# SCH.net
KiCad netlist of a schematic drawn in Altium Designer
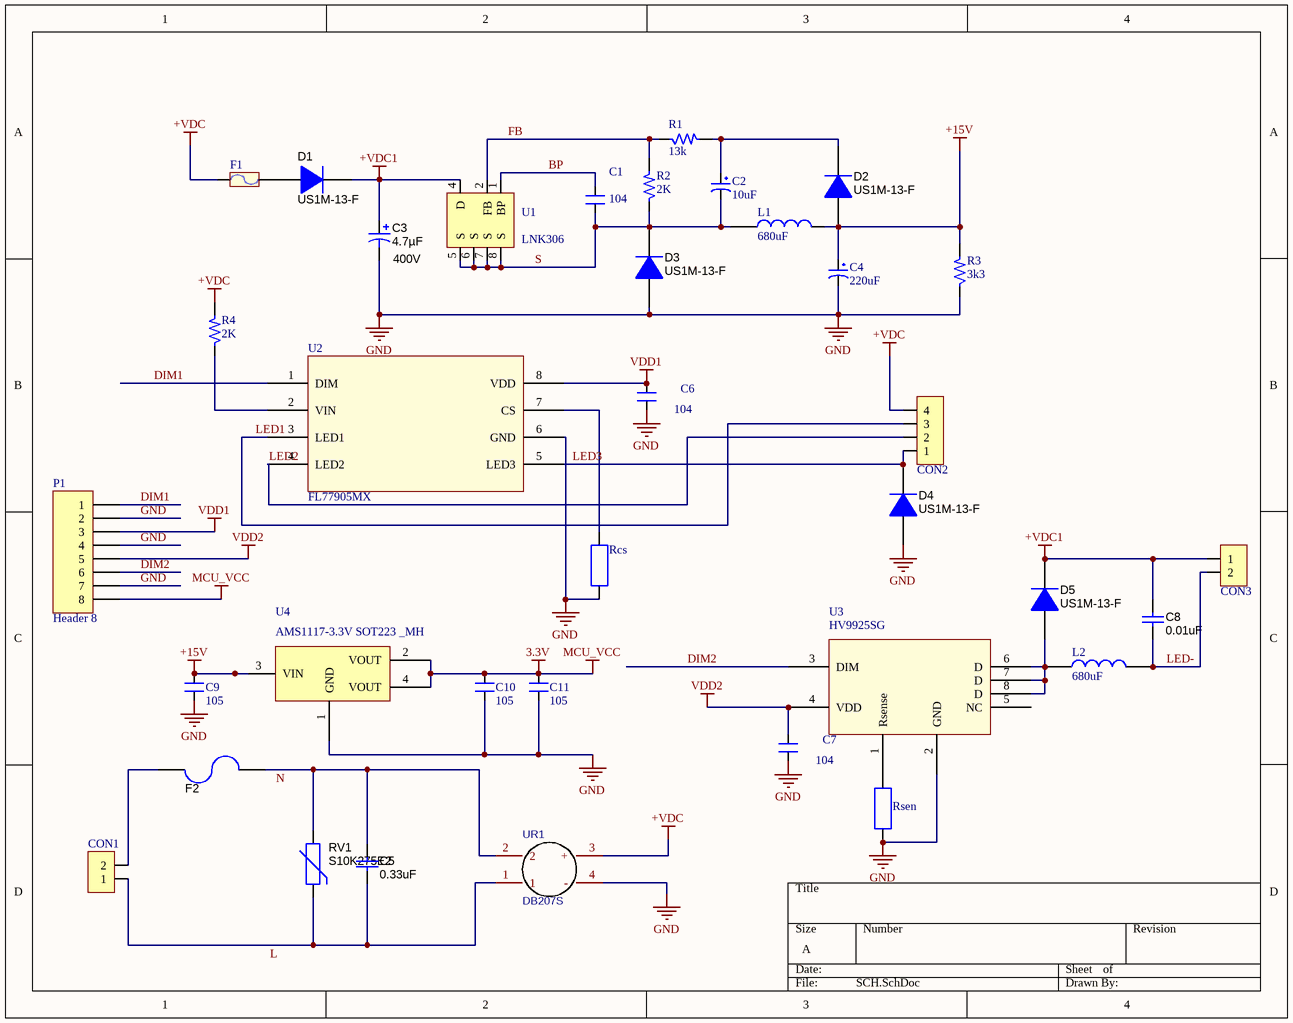
[diagram p0: SCH.SchDoc]

(export (version "E")
  (design (tool "Eeschema 10.0.6"))
  (components
    (comp (ref "C1")
      (value "104")
      (footprint "0805_Cap")
      (description "Cap SMD")
      (libsource (lib "hatcatbietbay") (part "CM"))
    )
    (comp (ref "C2")
      (value "10uF")
      (footprint "TU_NHOM_10uF_MH")
      (description "TU_NHOM_10uF_25V_MH")
      (libsource (lib "MH_DA_THU_VIEN_16122016") (part "TU_NHOM_10uF_25V_MH"))
    )
    (comp (ref "C3")
      (value "400AX6R8M8x11")
      (footprint "CAP-PANACAP-G-GENERIC")
      (description "CAP, AL, 6.8uF, 400V, +/-20%, TH")
      (fields
        (field (name "VALUEDISPLAYED") "4.7µF")
        (field (name "MANUFACTURER") "Rubycon")
        (field (name "VALUE2") "400V")
        (field (name "PUBLISHER") "Texas Instruments")
      )
      (libsource (lib "Capacitor_Aluminum") (part "400AX6R8M8x11"))
    )
    (comp (ref "C4")
      (value "220uF")
      (footprint "TU_NHOM_2.5_MH")
      (description "TU_NHOM_220uF_25V_MH")
      (libsource (lib "MH_DA_THU_VIEN_16122016") (part "TU_NHOM_220uF_25V_MH"))
    )
    (comp (ref "C5")
      (value "0.33uF")
      (footprint "B32922_12mm")
      (description "CAP FILM 0.33UF 630VDC RADIAL")
      (fields
        (field (name "PARTNUMBER") "B32922C3334M189")
        (field (name "MANUFACTURER") "EPCOS(TDK)")
        (field (name "SYMBOLCREATOR") "x0199378")
      )
      (libsource (lib "All-Final Symbols") (part "BFC233620154"))
    )
    (comp (ref "C6")
      (value "104")
      (footprint "0805_HV")
      (description "Cap SMD")
      (libsource (lib "hatcatbietbay") (part "CM"))
    )
    (comp (ref "C7")
      (value "104")
      (footprint "0805_HV")
      (description "Cap SMD")
      (libsource (lib "hatcatbietbay") (part "CM"))
    )
    (comp (ref "C8")
      (value "0.01uF")
      (footprint "B32922_12mm")
      (description "CAP FILM 0.33UF 630VDC RADIAL")
      (fields
        (field (name "PARTNUMBER") "B32922C3334M189")
        (field (name "MANUFACTURER") "EPCOS(TDK)")
        (field (name "SYMBOLCREATOR") "x0199378")
      )
      (libsource (lib "All-Final Symbols") (part "BFC233620154"))
    )
    (comp (ref "C9")
      (value "105")
      (footprint "0805_HV")
      (description "Cap SMD")
      (libsource (lib "hatcatbietbay") (part "CM"))
    )
    (comp (ref "C10")
      (value "105")
      (footprint "0805_HV")
      (description "Cap SMD")
      (libsource (lib "hatcatbietbay") (part "CM"))
    )
    (comp (ref "C11")
      (value "105")
      (footprint "0805_HV")
      (description "Cap SMD")
      (libsource (lib "hatcatbietbay") (part "CM"))
    )
    (comp (ref "CON1")
      (value "CON 2 EDG 5.08_MH")
      (footprint "CON 2 EDG 5.08")
      (description "CON 2 EDG 5.08 (xanh cong)")
      (libsource (lib "mySch") (part "CON 2 EDG 5.08_MH"))
    )
    (comp (ref "CON2")
      (value "CON 4 EDG 5.08_MH")
      (footprint "Con 4 EDG 5.08")
      (description "CON 4 EDG 5.08 (xanh cong)")
      (libsource (lib "MH_DA_THU_VIEN_16122016") (part "CON 4 EDG 5.08_MH"))
    )
    (comp (ref "CON3")
      (value "CON 2 EDG 5.08_MH")
      (footprint "CON 2 EDG 5.08")
      (description "CON 2 EDG 5.08 (xanh cong)")
      (libsource (lib "") (part "CON 2 EDG 5.08_MH_1"))
    )
    (comp (ref "D1")
      (value "US1M-13-F")
      (footprint "SMB")
      (description "Diode, Ultrafast, 600V, 1A, SMB")
      (fields
        (field (name "PARTNUMBER") "US1M-13-F")
        (field (name "MANUFACTURER") "Diodes Inc.")
        (field (name "PUBLISHER") "Texas Instruments")
      )
      (libsource (lib "Diode") (part "MURS160-13-F"))
    )
    (comp (ref "D2")
      (value "US1M-13-F")
      (footprint "SMB")
      (description "Diode, Ultrafast, 600V, 1A, SMB")
      (fields
        (field (name "PARTNUMBER") "US1M-13-F")
        (field (name "MANUFACTURER") "Diodes Inc.")
        (field (name "PUBLISHER") "Texas Instruments")
      )
      (libsource (lib "Diode") (part "MURS160-13-F"))
    )
    (comp (ref "D3")
      (value "US1M-13-F")
      (footprint "SMB")
      (description "Diode, Ultrafast, 600V, 1A, SMB")
      (fields
        (field (name "PARTNUMBER") "US1M-13-F")
        (field (name "MANUFACTURER") "Diodes Inc.")
        (field (name "PUBLISHER") "Texas Instruments")
      )
      (libsource (lib "Diode") (part "MURS160-13-F"))
    )
    (comp (ref "D4")
      (value "US1M-13-F")
      (footprint "SMB")
      (description "Diode, Ultrafast, 600V, 1A, SMB")
      (fields
        (field (name "PARTNUMBER") "US1M-13-F")
        (field (name "MANUFACTURER") "Diodes Inc.")
        (field (name "PUBLISHER") "Texas Instruments")
      )
      (libsource (lib "Diode") (part "MURS160-13-F"))
    )
    (comp (ref "D5")
      (value "US1M-13-F")
      (footprint "SMB")
      (description "Diode, Ultrafast, 600V, 1A, SMB")
      (fields
        (field (name "PARTNUMBER") "US1M-13-F")
        (field (name "MANUFACTURER") "Diodes Inc.")
        (field (name "PUBLISHER") "Texas Instruments")
      )
      (libsource (lib "Diode") (part "MURS160-13-F"))
    )
    (comp (ref "F1")
      (value "FUSE_AUTO_0.5A 8V 1206_MH")
      (footprint "FUSE 1206")
      (description "Fuse")
      (libsource (lib "MH_DA_THU_VIEN_16122016") (part "FUSE_AUTO_0.5A 8V 1206_MH"))
    )
    (comp (ref "F2")
      (value "37015000430")
      (footprint "Fuse 5x20")
      (description "FUSE BOARD MOUNT 5A 250VAC RAD")
      (fields (field (name "MANUFACTURER") "Littelfuse Inc") (field (name "PUBLISHER") "Texas Instruments"))
      (libsource (lib "Fuse") (part "0216008.MXESPP"))
    )
    (comp (ref "L1")
      (value "680uF")
      (footprint "Inductor 4.5x5")
      (libsource (lib "MH_DA_THU_VIEN_16122016") (part "Inductor 4.5x5_MH"))
    )
    (comp (ref "L2")
      (value "680uF")
      (footprint "Inductor 4.5x5")
      (libsource (lib "MH_DA_THU_VIEN_16122016") (part "Inductor 4.5x5_MH"))
    )
    (comp (ref "P1")
      (value "Header 8")
      (footprint "HDR1X8")
      (description "Header, 8-Pin")
      (fields (field (name "PUBLISHER") "Altium Limited"))
      (libsource (lib "Miscellaneous Connectors") (part "Header 8"))
    )
    (comp (ref "R1")
      (value "13k")
      (footprint "0805_R")
      (description "Resistor 1/4W")
      (libsource (lib "hatcatbietbay") (part "R"))
    )
    (comp (ref "R2")
      (value "2K")
      (footprint "0805_R")
      (description "Resistor 1/4W")
      (libsource (lib "hatcatbietbay") (part "R"))
    )
    (comp (ref "R3")
      (value "3k3")
      (footprint "0805_R")
      (description "Resistor 1/4W")
      (libsource (lib "hatcatbietbay") (part "R"))
    )
    (comp (ref "R4")
      (value "2K")
      (footprint "1206")
      (description "Resistor 1/4W")
      (libsource (lib "hatcatbietbay") (part "R"))
    )
    (comp (ref "Rcs")
      (value "TRO_CS_2W_MH")
      (footprint "TRO_VACH_2W")
      (libsource (lib "MH_DA_THU_VIEN_16122016") (part "TRO_CS_2W_MH"))
    )
    (comp (ref "Rsen")
      (value "TRO_CS_2W_MH")
      (footprint "TRO_VACH_2W")
      (libsource (lib "MH_DA_THU_VIEN_16122016") (part "TRO_CS_2W_MH"))
    )
    (comp (ref "RV1")
      (value "S10K275E2")
      (footprint "VAR_S10K275E2")
      (description "Varistor 275V RMS 10MM Radial, TH")
      (fields
        (field (name "MANUFACTURER") "EPCOS Inc")
        (field (name "SYMBOLCREATOR") "a0412235")
        (field (name "PUBLISHER") "Texas Instruments")
      )
      (libsource (lib "Other_Passive") (part "S10K275E2"))
    )
    (comp (ref "U1") (value "LNK306") (footprint "SOP 7") (libsource (lib "LNK304") (part "Component_1")))
    (comp (ref "U2") (value "FL77905MX") (footprint "SOP 8") (libsource (lib "Schlib1") (part "FL77905")))
    (comp (ref "U3") (value "HV9925SG") (footprint "SOP 8") (libsource (lib "Schlib1") (part "HV9925")))
    (comp (ref "U4")
      (value "AMS1117-3.3V SOT223 _MH")
      (footprint "SOT223")
      (libsource (lib "MH_DA_THU_VIEN_16122016") (part "AMS1117-3.3V SOT223 _MH"))
    )
    (comp (ref "UR1")
      (value "DB207S")
      (footprint "DB207S")
      (fields (field (name "BOM_SUPPLIER PART") "C84160"))
      (libsource (lib "mySch") (part "DB207S"))
    )
  )
  (nets
    (net (code "1") (name "+15V") (class "Default")
      (node (ref "C4") (pin "1") (pinfunction "1_1") (pintype "passive"))
      (node (ref "C9") (pin "2") (pinfunction "2_2") (pintype "passive"))
      (node (ref "D2") (pin "2") (pinfunction "A_2") (pintype "passive"))
      (node (ref "L1") (pin "2") (pinfunction "2_2") (pintype "passive"))
      (node (ref "R3") (pin "2") (pinfunction "2_2") (pintype "passive"))
      (node (ref "U4") (pin "3") (pinfunction "VIN_3") (pintype "passive"))
    )
    (net (code "2") (name "+VDC") (class "Default")
      (node (ref "CON2") (pin "4") (pinfunction "4_4") (pintype "passive"))
      (node (ref "F1") (pin "1") (pinfunction "1_1") (pintype "passive"))
      (node (ref "R4") (pin "2") (pinfunction "2_2") (pintype "passive"))
      (node (ref "UR1") (pin "3") (pinfunction "+_3") (pintype "passive"))
    )
    (net (code "3") (name "+VDC1") (class "Default")
      (node (ref "C3") (pin "1") (pinfunction "+_1") (pintype "passive"))
      (node (ref "C8") (pin "2") (pinfunction "2_2") (pintype "passive"))
      (node (ref "CON3") (pin "1") (pinfunction "1_1") (pintype "passive"))
      (node (ref "D1") (pin "1") (pinfunction "K_1") (pintype "passive"))
      (node (ref "D5") (pin "1") (pinfunction "K_1") (pintype "passive"))
      (node (ref "U1") (pin "4") (pinfunction "D_4") (pintype "passive"))
    )
    (net (code "4") (name "/BP") (class "Default")
      (node (ref "C1") (pin "2") (pinfunction "2_2") (pintype "passive"))
      (node (ref "U1") (pin "1") (pinfunction "BP_1") (pintype "passive"))
    )
    (net (code "5") (name "/DIM1") (class "Default")
      (node (ref "P1") (pin "1") (pinfunction "1_1") (pintype "passive"))
      (node (ref "U2") (pin "1") (pinfunction "DIM_1") (pintype "passive"))
    )
    (net (code "6") (name "/DIM2") (class "Default")
      (node (ref "P1") (pin "6") (pinfunction "6_6") (pintype "passive"))
      (node (ref "U3") (pin "3") (pinfunction "DIM_3") (pintype "passive"))
    )
    (net (code "7") (name "/FB") (class "Default")
      (node (ref "R1") (pin "1") (pinfunction "1_1") (pintype "passive"))
      (node (ref "R2") (pin "2") (pinfunction "2_2") (pintype "passive"))
      (node (ref "U1") (pin "2") (pinfunction "FB_2") (pintype "passive"))
    )
    (net (code "8") (name "/L") (class "Default")
      (node (ref "C5") (pin "1") (pinfunction "1_1") (pintype "passive"))
      (node (ref "CON1") (pin "1") (pinfunction "1_1") (pintype "passive"))
      (node (ref "RV1") (pin "2") (pinfunction "2_2") (pintype "passive"))
      (node (ref "UR1") (pin "1") (pinfunction "1_1") (pintype "passive"))
    )
    (net (code "9") (name "/LED-") (class "Default")
      (node (ref "C8") (pin "1") (pinfunction "1_1") (pintype "passive"))
      (node (ref "CON3") (pin "2") (pinfunction "2_2") (pintype "passive"))
      (node (ref "L2") (pin "2") (pinfunction "2_2") (pintype "passive"))
    )
    (net (code "10") (name "/LED1") (class "Default")
      (node (ref "CON2") (pin "3") (pinfunction "3_3") (pintype "passive"))
      (node (ref "U2") (pin "3") (pinfunction "LED1_3") (pintype "passive"))
    )
    (net (code "11") (name "/LED2") (class "Default")
      (node (ref "CON2") (pin "2") (pinfunction "2_2") (pintype "passive"))
      (node (ref "U2") (pin "4") (pinfunction "LED2_4") (pintype "passive"))
    )
    (net (code "12") (name "/LED3") (class "Default")
      (node (ref "CON2") (pin "1") (pinfunction "1_1") (pintype "passive"))
      (node (ref "D4") (pin "1") (pinfunction "K_1") (pintype "passive"))
      (node (ref "U2") (pin "5") (pinfunction "LED3_5") (pintype "passive"))
    )
    (net (code "13") (name "/N") (class "Default")
      (node (ref "C5") (pin "2") (pinfunction "2_2") (pintype "passive"))
      (node (ref "F2") (pin "1") (pinfunction "1_1") (pintype "passive"))
      (node (ref "RV1") (pin "1") (pinfunction "1_1") (pintype "passive"))
      (node (ref "UR1") (pin "2") (pinfunction "2_2") (pintype "passive"))
    )
    (net (code "14") (name "/S") (class "Default")
      (node (ref "C1") (pin "1") (pinfunction "1_1") (pintype "passive"))
      (node (ref "C2") (pin "2") (pinfunction "2_2") (pintype "passive"))
      (node (ref "D3") (pin "1") (pinfunction "K_1") (pintype "passive"))
      (node (ref "L1") (pin "1") (pinfunction "1_1") (pintype "passive"))
      (node (ref "R2") (pin "1") (pinfunction "1_1") (pintype "passive"))
      (node (ref "U1") (pin "5") (pinfunction "S_5") (pintype "passive"))
      (node (ref "U1") (pin "6") (pinfunction "S_6") (pintype "passive"))
      (node (ref "U1") (pin "7") (pinfunction "S_7") (pintype "passive"))
      (node (ref "U1") (pin "8") (pinfunction "S_8") (pintype "passive"))
    )
    (net (code "15") (name "3.3V") (class "Default")
      (node (ref "C10") (pin "2") (pinfunction "2_2") (pintype "passive"))
      (node (ref "C11") (pin "2") (pinfunction "2_2") (pintype "passive"))
      (node (ref "P1") (pin "8") (pinfunction "8_8") (pintype "passive"))
      (node (ref "U4") (pin "2") (pinfunction "VOUT_2") (pintype "passive"))
      (node (ref "U4") (pin "4") (pinfunction "VOUT_4") (pintype "passive"))
    )
    (net (code "16") (name "GND") (class "Default")
      (node (ref "C10") (pin "1") (pinfunction "1_1") (pintype "passive"))
      (node (ref "C11") (pin "1") (pinfunction "1_1") (pintype "passive"))
      (node (ref "C3") (pin "2") (pinfunction "-_2") (pintype "passive"))
      (node (ref "C4") (pin "2") (pinfunction "2_2") (pintype "passive"))
      (node (ref "C6") (pin "1") (pinfunction "1_1") (pintype "passive"))
      (node (ref "C7") (pin "1") (pinfunction "1_1") (pintype "passive"))
      (node (ref "C9") (pin "1") (pinfunction "1_1") (pintype "passive"))
      (node (ref "D3") (pin "2") (pinfunction "A_2") (pintype "passive"))
      (node (ref "D4") (pin "2") (pinfunction "A_2") (pintype "passive"))
      (node (ref "P1") (pin "2") (pinfunction "2_2") (pintype "passive"))
      (node (ref "P1") (pin "4") (pinfunction "4_4") (pintype "passive"))
      (node (ref "P1") (pin "7") (pinfunction "7_7") (pintype "passive"))
      (node (ref "R3") (pin "1") (pinfunction "1_1") (pintype "passive"))
      (node (ref "Rcs") (pin "1") (pinfunction "1_1") (pintype "passive"))
      (node (ref "Rsen") (pin "1") (pinfunction "1_1") (pintype "passive"))
      (node (ref "U2") (pin "6") (pinfunction "GND_6") (pintype "passive"))
      (node (ref "U3") (pin "2") (pinfunction "GND_2") (pintype "passive"))
      (node (ref "U4") (pin "1") (pinfunction "GND_1") (pintype "passive"))
      (node (ref "UR1") (pin "4") (pinfunction "-_4") (pintype "passive"))
    )
    (net (code "17") (name "Net-(CON1-Pad2)") (class "Default")
      (node (ref "CON1") (pin "2") (pinfunction "2_2") (pintype "passive"))
      (node (ref "F2") (pin "2") (pinfunction "2_2") (pintype "passive"))
    )
    (net (code "18") (name "Net-(D1-A)") (class "Default")
      (node (ref "D1") (pin "2") (pinfunction "A_2") (pintype "passive"))
      (node (ref "F1") (pin "2") (pinfunction "2_2") (pintype "passive"))
    )
    (net (code "19") (name "Net-(D2-K)") (class "Default")
      (node (ref "C2") (pin "1") (pinfunction "1_1") (pintype "passive"))
      (node (ref "D2") (pin "1") (pinfunction "K_1") (pintype "passive"))
      (node (ref "R1") (pin "2") (pinfunction "2_2") (pintype "passive"))
    )
    (net (code "20") (name "Net-(D5-A)") (class "Default")
      (node (ref "D5") (pin "2") (pinfunction "A_2") (pintype "passive"))
      (node (ref "L2") (pin "1") (pinfunction "1_1") (pintype "passive"))
      (node (ref "U3") (pin "6") (pinfunction "D_6") (pintype "passive"))
      (node (ref "U3") (pin "7") (pinfunction "D_7") (pintype "passive"))
      (node (ref "U3") (pin "8") (pinfunction "D_8") (pintype "passive"))
    )
    (net (code "21") (name "Net-(U2-CS)") (class "Default")
      (node (ref "Rcs") (pin "2") (pinfunction "2_2") (pintype "passive"))
      (node (ref "U2") (pin "7") (pinfunction "CS_7") (pintype "passive"))
    )
    (net (code "22") (name "Net-(U2-VIN)") (class "Default")
      (node (ref "R4") (pin "1") (pinfunction "1_1") (pintype "passive"))
      (node (ref "U2") (pin "2") (pinfunction "VIN_2") (pintype "passive"))
    )
    (net (code "23") (name "Net-(U3-Rsense)") (class "Default")
      (node (ref "Rsen") (pin "2") (pinfunction "2_2") (pintype "passive"))
      (node (ref "U3") (pin "1") (pinfunction "Rsense_1") (pintype "passive"))
    )
    (net (code "24") (name "VDD1") (class "Default")
      (node (ref "C6") (pin "2") (pinfunction "2_2") (pintype "passive"))
      (node (ref "P1") (pin "3") (pinfunction "3_3") (pintype "passive"))
      (node (ref "U2") (pin "8") (pinfunction "VDD_8") (pintype "passive"))
    )
    (net (code "25") (name "VDD2") (class "Default")
      (node (ref "C7") (pin "2") (pinfunction "2_2") (pintype "passive"))
      (node (ref "P1") (pin "5") (pinfunction "5_5") (pintype "passive"))
      (node (ref "U3") (pin "4") (pinfunction "VDD_4") (pintype "passive"))
    )
    (net (code "26") (name "unconnected-(U3-NC-Pad5)") (class "Default")
      (node (ref "U3") (pin "5") (pinfunction "NC_5") (pintype "passive"))
    )
  )
)
